# Schematic.net
KiCad netlist of a schematic drawn in EasyEDA Pro
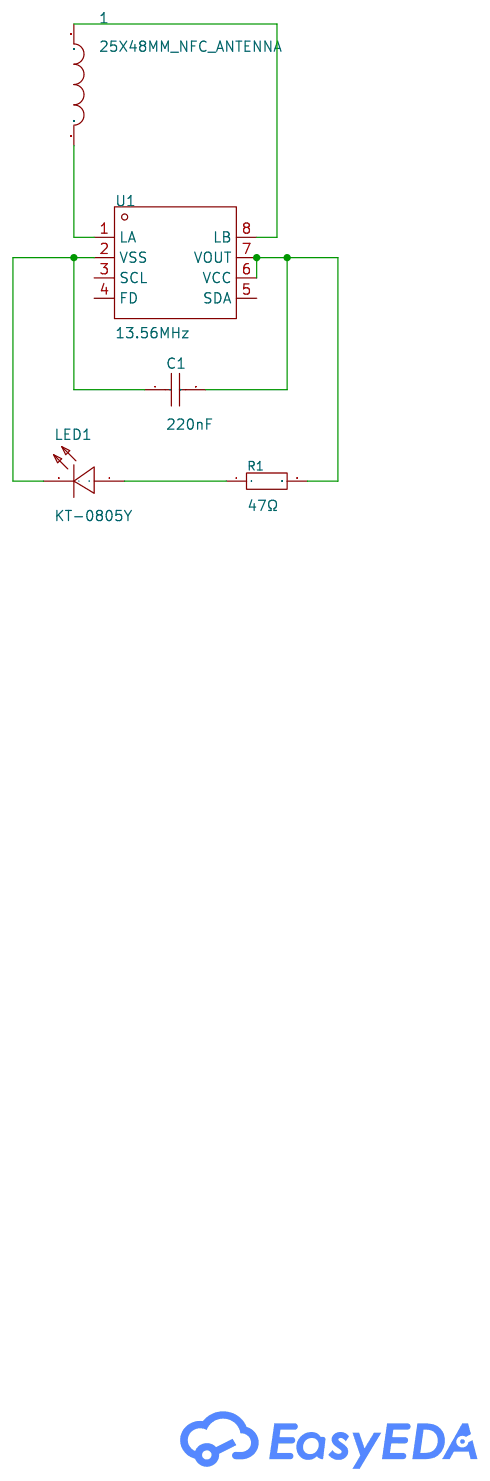
[diagram p0: schematic sheet]

(export (version "E")
  (design (tool "Eeschema 10.0.6"))
  (components
    (comp (ref "1")
      (value "25X48MM_NFC_ANTENNA")
      (footprint "easyedapro:25X48MM_NFC_ANTENNA")
      (libsource (lib "easyedapro") (part "25X48MM_NFC_ANTENNA"))
    )
    (comp (ref "C1")
      (value "220nF")
      (footprint "easyedapro:C0603")
      (description "Capacitance:220nF Tolerance:±10% Tolerance:±10% Voltage Rating:25V Temperature Coefficient:X7R")
      (fields
        (field (name "Manufacturer Part") "CL10B224KA8NNNC")
        (field (name "Manufacturer") "SAMSUNG(三星)")
      )
      (libsource (lib "easyedapro") (part "CL10B224KA8NNNC"))
    )
    (comp (ref "LED1")
      (value "KT-0805Y")
      (footprint "easyedapro:LED0805-R-RD")
      (fields (field (name "Manufacturer") "KENTO"))
      (libsource (lib "easyedapro") (part "17-21SUYC/TR8"))
    )
    (comp (ref "R1")
      (value "47Ω")
      (footprint "easyedapro:R0603")
      (fields
        (field (name "Manufacturer Part") "0603WAF470JT5E")
        (field (name "Manufacturer") "UNI-ROYAL(厚声)")
      )
      (libsource (lib "easyedapro") (part "0603WAF470JT5E"))
    )
    (comp (ref "U1")
      (value "13.56MHz")
      (footprint "easyedapro:XQFN-8_L1.6-W1.6-P0.50-BL_NT3H2111W0FHKH")
      (fields (field (name "Manufacturer Part") "NT3H2111W0FHKH") (field (name "Manufacturer") "NXP(恩智浦)"))
      (libsource (lib "easyedapro") (part "NT3H2111W0FHKH"))
    )
  )
  (nets
    (net (code "1") (name "Net-(LED1-+)") (class "Default")
      (node (ref "LED1") (pin "1") (pinfunction "+_1") (pintype "unspecified"))
      (node (ref "R1") (pin "1") (pinfunction "1_1") (pintype "input"))
    )
    (net (code "2") (name "Net-(LED1--)") (class "Default")
      (node (ref "C1") (pin "1") (pinfunction "1_1") (pintype "input"))
      (node (ref "LED1") (pin "2") (pinfunction "-_2") (pintype "unspecified"))
      (node (ref "U1") (pin "2") (pinfunction "VSS_2") (pintype "unspecified"))
    )
    (net (code "3") (name "Net-(U1-LA)") (class "Default")
      (node (ref "1") (pin "P$2") (pinfunction "P$2_P$2") (pintype "bidirectional"))
      (node (ref "U1") (pin "1") (pinfunction "LA_1") (pintype "unspecified"))
    )
    (net (code "4") (name "Net-(U1-LB)") (class "Default")
      (node (ref "1") (pin "P$1") (pinfunction "P$1_P$1") (pintype "bidirectional"))
      (node (ref "U1") (pin "8") (pinfunction "LB_8") (pintype "unspecified"))
    )
    (net (code "5") (name "Net-(U1-VCC)") (class "Default")
      (node (ref "C1") (pin "2") (pinfunction "2_2") (pintype "input"))
      (node (ref "R1") (pin "2") (pinfunction "2_2") (pintype "input"))
      (node (ref "U1") (pin "6") (pinfunction "VCC_6") (pintype "unspecified"))
      (node (ref "U1") (pin "7") (pinfunction "VOUT_7") (pintype "unspecified"))
    )
    (net (code "6") (name "unconnected-(U1-FD-Pad4)") (class "Default")
      (node (ref "U1") (pin "4") (pinfunction "FD_4") (pintype "unspecified"))
    )
    (net (code "7") (name "unconnected-(U1-SCL-Pad3)") (class "Default")
      (node (ref "U1") (pin "3") (pinfunction "SCL_3") (pintype "unspecified"))
    )
    (net (code "8") (name "unconnected-(U1-SDA-Pad5)") (class "Default")
      (node (ref "U1") (pin "5") (pinfunction "SDA_5") (pintype "unspecified"))
    )
  )
)
